# bb_preamp.net
KiCad netlist of a schematic drawn in EAGLE
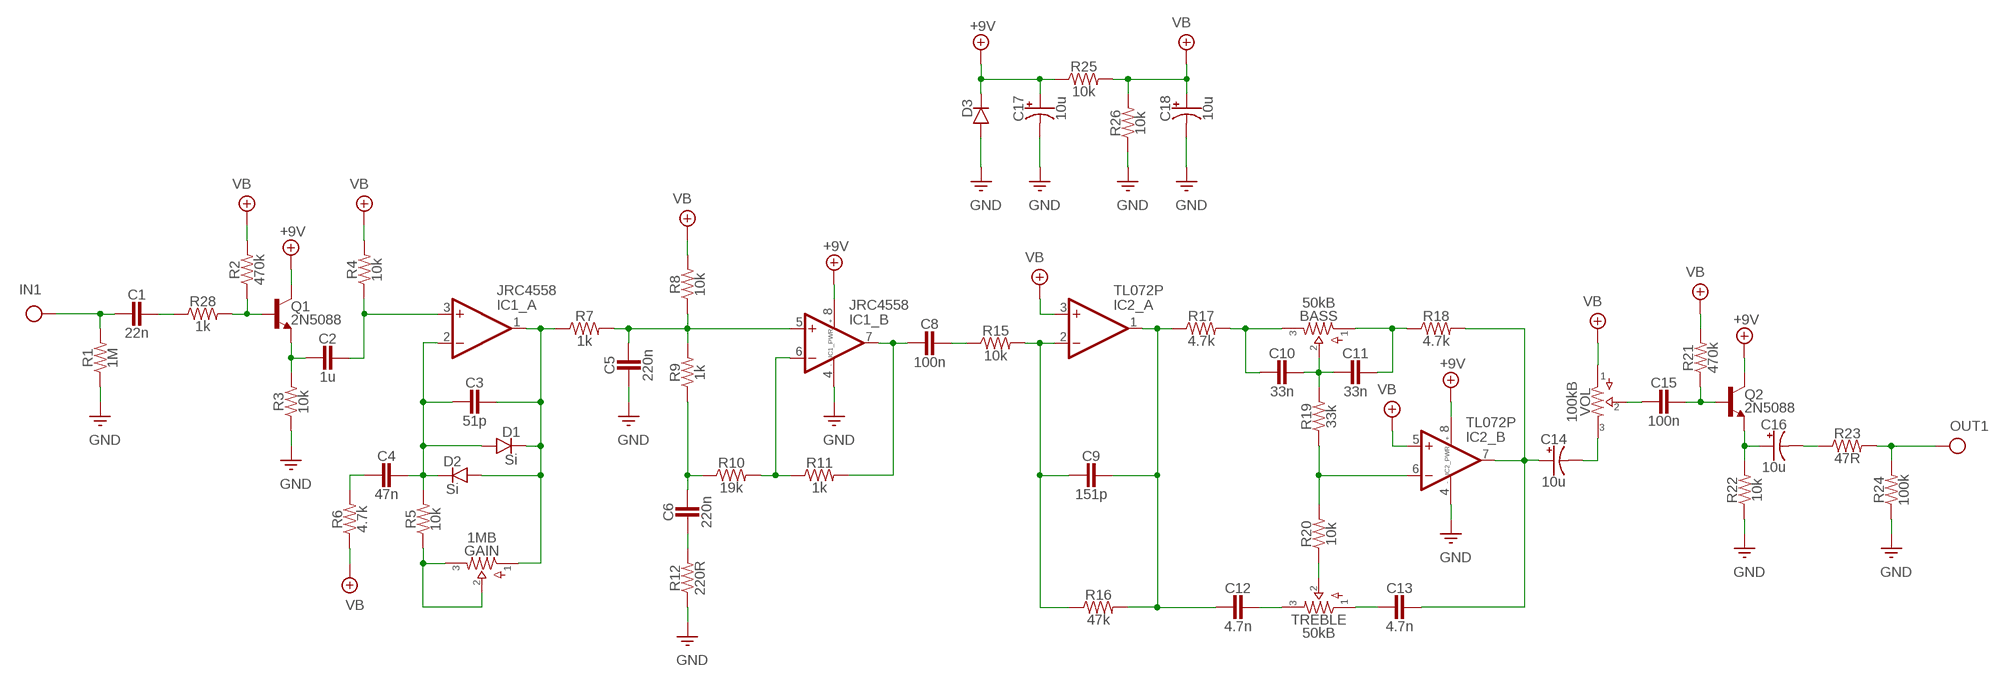
[diagram p0: schematic, sheet 1]

(export (version "E")
  (design (tool "Eeschema 10.0.6"))
  (components
    (comp (ref "BASS")
      (value "50kB")
      (footprint "eagle-import:16MM")
      (libsource (lib "eagle-import") (part "POTS16MM"))
    )
    (comp (ref "C1")
      (value "22n")
      (footprint "eagle-import:BOX_SMALL")
      (libsource (lib "eagle-import") (part "CER/FILMBOX.1"))
    )
    (comp (ref "C2")
      (value "1u")
      (footprint "eagle-import:BOX_SMALL")
      (libsource (lib "eagle-import") (part "CER/FILMBOX.1"))
    )
    (comp (ref "C3")
      (value "51p")
      (footprint "eagle-import:BOX_SMALL")
      (libsource (lib "eagle-import") (part "CER/FILMBOX.1"))
    )
    (comp (ref "C4")
      (value "47n")
      (footprint "eagle-import:BOX_SMALL")
      (libsource (lib "eagle-import") (part "CER/FILMBOX.1"))
    )
    (comp (ref "C5")
      (value "220n")
      (footprint "eagle-import:BOX_SMALL")
      (libsource (lib "eagle-import") (part "CER/FILMBOX.1"))
    )
    (comp (ref "C6")
      (value "220n")
      (footprint "eagle-import:BOX_SMALL")
      (libsource (lib "eagle-import") (part "CER/FILMBOX.1"))
    )
    (comp (ref "C8")
      (value "100n")
      (footprint "eagle-import:BOX_SMALL")
      (libsource (lib "eagle-import") (part "CER/FILMBOX.1"))
    )
    (comp (ref "C9")
      (value "151p")
      (footprint "eagle-import:BOX_SMALL")
      (libsource (lib "eagle-import") (part "CER/FILMBOX.1"))
    )
    (comp (ref "C10")
      (value "33n")
      (footprint "eagle-import:BOX_SMALL")
      (libsource (lib "eagle-import") (part "CER/FILMBOX.1"))
    )
    (comp (ref "C11")
      (value "33n")
      (footprint "eagle-import:BOX_SMALL")
      (libsource (lib "eagle-import") (part "CER/FILMBOX.1"))
    )
    (comp (ref "C12")
      (value "4.7n")
      (footprint "eagle-import:BOX_SMALL")
      (libsource (lib "eagle-import") (part "CER/FILMBOX.1"))
    )
    (comp (ref "C13")
      (value "4.7n")
      (footprint "eagle-import:BOX_SMALL")
      (libsource (lib "eagle-import") (part "CER/FILMBOX.1"))
    )
    (comp (ref "C14")
      (value "10u")
      (footprint "eagle-import:050_020")
      (libsource (lib "eagle-import") (part "0500"))
    )
    (comp (ref "C15")
      (value "100n")
      (footprint "eagle-import:BOX_SMALL")
      (libsource (lib "eagle-import") (part "CER/FILMBOX.1"))
    )
    (comp (ref "C16")
      (value "10u")
      (footprint "eagle-import:050_020")
      (libsource (lib "eagle-import") (part "0500"))
    )
    (comp (ref "C17")
      (value "10u")
      (footprint "eagle-import:050_020")
      (libsource (lib "eagle-import") (part "0500"))
    )
    (comp (ref "C18")
      (value "10u")
      (footprint "eagle-import:050_020")
      (libsource (lib "eagle-import") (part "0500"))
    )
    (comp (ref "D1")
      (value "Si")
      (footprint "eagle-import:DO35-2")
      (libsource (lib "eagle-import") (part "DO35.2"))
    )
    (comp (ref "D2")
      (value "Si")
      (footprint "eagle-import:DO35-2")
      (libsource (lib "eagle-import") (part "DO35.2"))
    )
    (comp (ref "D3")
      (value "DO41.3")
      (footprint "eagle-import:DO41-3")
      (libsource (lib "eagle-import") (part "DO41.3"))
    )
    (comp (ref "GAIN")
      (value "1MB")
      (footprint "eagle-import:16MM")
      (libsource (lib "eagle-import") (part "POTS16MM"))
    )
    (comp (ref "IC1")
      (value "JRC4558")
      (footprint "eagle-import:DIL0")
      (libsource (lib "eagle-import") (part "DUALTH"))
    )
    (comp (ref "IC2")
      (value "TL072P")
      (footprint "eagle-import:DIL0")
      (libsource (lib "eagle-import") (part "DUALTH"))
    )
    (comp (ref "Q1")
      (value "2N5088")
      (footprint "eagle-import:TO92-")
      (libsource (lib "eagle-import") (part "2N5088"))
    )
    (comp (ref "Q2")
      (value "2N5088")
      (footprint "eagle-import:TO92-")
      (libsource (lib "eagle-import") (part "2N5088"))
    )
    (comp (ref "R1")
      (value "1M")
      (footprint "eagle-import:R0207_3")
      (libsource (lib "eagle-import") (part "R_.3B"))
    )
    (comp (ref "R2")
      (value "470k")
      (footprint "eagle-import:R0207_3")
      (libsource (lib "eagle-import") (part "R_.3B"))
    )
    (comp (ref "R3")
      (value "10k")
      (footprint "eagle-import:R0207_3")
      (libsource (lib "eagle-import") (part "R_.3B"))
    )
    (comp (ref "R4")
      (value "10k")
      (footprint "eagle-import:R0207_3")
      (libsource (lib "eagle-import") (part "R_.3B"))
    )
    (comp (ref "R5")
      (value "10k")
      (footprint "eagle-import:R0207_3")
      (libsource (lib "eagle-import") (part "R_.3B"))
    )
    (comp (ref "R6")
      (value "4.7k")
      (footprint "eagle-import:R0207_3")
      (libsource (lib "eagle-import") (part "R_.3B"))
    )
    (comp (ref "R7")
      (value "1k")
      (footprint "eagle-import:R0207_3")
      (libsource (lib "eagle-import") (part "R_.3B"))
    )
    (comp (ref "R8")
      (value "10k")
      (footprint "eagle-import:R0207_3")
      (libsource (lib "eagle-import") (part "R_.3B"))
    )
    (comp (ref "R9")
      (value "1k")
      (footprint "eagle-import:R0207_3")
      (libsource (lib "eagle-import") (part "R_.3B"))
    )
    (comp (ref "R10")
      (value "19k")
      (footprint "eagle-import:R0207_3")
      (libsource (lib "eagle-import") (part "R_.3B"))
    )
    (comp (ref "R11")
      (value "1k")
      (footprint "eagle-import:R0207_3")
      (libsource (lib "eagle-import") (part "R_.3B"))
    )
    (comp (ref "R12")
      (value "220R")
      (footprint "eagle-import:R0207_3")
      (libsource (lib "eagle-import") (part "R_.3B"))
    )
    (comp (ref "R15")
      (value "10k")
      (footprint "eagle-import:R0207_3")
      (libsource (lib "eagle-import") (part "R_.3B"))
    )
    (comp (ref "R16")
      (value "47k")
      (footprint "eagle-import:R0207_3")
      (libsource (lib "eagle-import") (part "R_.3B"))
    )
    (comp (ref "R17")
      (value "4.7k")
      (footprint "eagle-import:R0207_3")
      (libsource (lib "eagle-import") (part "R_.3B"))
    )
    (comp (ref "R18")
      (value "4.7k")
      (footprint "eagle-import:R0207_3")
      (libsource (lib "eagle-import") (part "R_.3B"))
    )
    (comp (ref "R19")
      (value "33k")
      (footprint "eagle-import:R0207_3")
      (libsource (lib "eagle-import") (part "R_.3B"))
    )
    (comp (ref "R20")
      (value "10k")
      (footprint "eagle-import:R0207_3")
      (libsource (lib "eagle-import") (part "R_.3B"))
    )
    (comp (ref "R21")
      (value "470k")
      (footprint "eagle-import:R0207_3")
      (libsource (lib "eagle-import") (part "R_.3B"))
    )
    (comp (ref "R22")
      (value "10k")
      (footprint "eagle-import:R0207_3")
      (libsource (lib "eagle-import") (part "R_.3B"))
    )
    (comp (ref "R23")
      (value "47R")
      (footprint "eagle-import:R0207_3")
      (libsource (lib "eagle-import") (part "R_.3B"))
    )
    (comp (ref "R24")
      (value "100k")
      (footprint "eagle-import:R0207_3")
      (libsource (lib "eagle-import") (part "R_.3B"))
    )
    (comp (ref "R25")
      (value "10k")
      (footprint "eagle-import:R0207_3")
      (libsource (lib "eagle-import") (part "R_.3B"))
    )
    (comp (ref "R26")
      (value "10k")
      (footprint "eagle-import:R0207_3")
      (libsource (lib "eagle-import") (part "R_.3B"))
    )
    (comp (ref "R28")
      (value "1k")
      (footprint "eagle-import:R0207_3")
      (libsource (lib "eagle-import") (part "R_.3B"))
    )
    (comp (ref "TREBLE")
      (value "50kB")
      (footprint "eagle-import:16MM")
      (libsource (lib "eagle-import") (part "POTS16MM"))
    )
    (comp (ref "VOL")
      (value "100kB")
      (footprint "eagle-import:16MM")
      (libsource (lib "eagle-import") (part "POTS16MM"))
    )
  )
  (nets
    (net (code "1") (name "+9V") (class "Default")
      (node (ref "C17") (pin "+") (pinfunction "+_+") (pintype "passive"))
      (node (ref "D3") (pin "C") (pinfunction "C_C") (pintype "passive"))
      (node (ref "IC1") (pin "8") (pinfunction "V+_8") (pintype "power_in"))
      (node (ref "IC2") (pin "8") (pinfunction "V+_8") (pintype "power_in"))
      (node (ref "Q1") (pin "1") (pinfunction "C_1") (pintype "passive"))
      (node (ref "Q2") (pin "1") (pinfunction "C_1") (pintype "passive"))
      (node (ref "R25") (pin "1") (pinfunction "1_1") (pintype "passive"))
    )
    (net (code "2") (name "GND") (class "Default")
      (node (ref "C17") (pin "-") (pinfunction "-_-") (pintype "passive"))
      (node (ref "C18") (pin "-") (pinfunction "-_-") (pintype "passive"))
      (node (ref "C5") (pin "2") (pinfunction "2_2") (pintype "passive"))
      (node (ref "D3") (pin "A") (pinfunction "A_A") (pintype "passive"))
      (node (ref "IC1") (pin "4") (pinfunction "V-_4") (pintype "power_in"))
      (node (ref "IC2") (pin "4") (pinfunction "V-_4") (pintype "power_in"))
      (node (ref "R1") (pin "1") (pinfunction "1_1") (pintype "passive"))
      (node (ref "R12") (pin "1") (pinfunction "1_1") (pintype "passive"))
      (node (ref "R22") (pin "1") (pinfunction "1_1") (pintype "passive"))
      (node (ref "R24") (pin "1") (pinfunction "1_1") (pintype "passive"))
      (node (ref "R26") (pin "1") (pinfunction "1_1") (pintype "passive"))
      (node (ref "R3") (pin "1") (pinfunction "1_1") (pintype "passive"))
    )
    (net (code "3") (name "IN") (class "Default")
      (node (ref "C1") (pin "2") (pinfunction "2_2") (pintype "passive"))
      (node (ref "R1") (pin "2") (pinfunction "2_2") (pintype "passive"))
    )
    (net (code "4") (name "Net-(BASS-Pad1)") (class "Default")
      (node (ref "BASS") (pin "1") (pinfunction "1_1") (pintype "passive"))
      (node (ref "C11") (pin "1") (pinfunction "1_1") (pintype "passive"))
      (node (ref "R18") (pin "1") (pinfunction "1_1") (pintype "passive"))
    )
    (net (code "5") (name "Net-(BASS-Pad2)") (class "Default")
      (node (ref "BASS") (pin "2") (pinfunction "2_2") (pintype "passive"))
      (node (ref "C10") (pin "1") (pinfunction "1_1") (pintype "passive"))
      (node (ref "C11") (pin "2") (pinfunction "2_2") (pintype "passive"))
      (node (ref "R19") (pin "2") (pinfunction "2_2") (pintype "passive"))
    )
    (net (code "6") (name "Net-(BASS-Pad3)") (class "Default")
      (node (ref "BASS") (pin "3") (pinfunction "3_3") (pintype "passive"))
      (node (ref "C10") (pin "2") (pinfunction "2_2") (pintype "passive"))
      (node (ref "R17") (pin "2") (pinfunction "2_2") (pintype "passive"))
    )
    (net (code "7") (name "Net-(C1-Pad1)") (class "Default")
      (node (ref "C1") (pin "1") (pinfunction "1_1") (pintype "passive"))
      (node (ref "R28") (pin "1") (pinfunction "1_1") (pintype "passive"))
    )
    (net (code "8") (name "Net-(C4-Pad2)") (class "Default")
      (node (ref "C4") (pin "2") (pinfunction "2_2") (pintype "passive"))
      (node (ref "R6") (pin "2") (pinfunction "2_2") (pintype "passive"))
    )
    (net (code "9") (name "Net-(C6-Pad1)") (class "Default")
      (node (ref "C6") (pin "1") (pinfunction "1_1") (pintype "passive"))
      (node (ref "R10") (pin "1") (pinfunction "1_1") (pintype "passive"))
      (node (ref "R9") (pin "1") (pinfunction "1_1") (pintype "passive"))
    )
    (net (code "10") (name "Net-(C6-Pad2)") (class "Default")
      (node (ref "C6") (pin "2") (pinfunction "2_2") (pintype "passive"))
      (node (ref "R12") (pin "2") (pinfunction "2_2") (pintype "passive"))
    )
    (net (code "11") (name "Net-(C8-Pad1)") (class "Default")
      (node (ref "C8") (pin "1") (pinfunction "1_1") (pintype "passive"))
      (node (ref "R15") (pin "1") (pinfunction "1_1") (pintype "passive"))
    )
    (net (code "12") (name "Net-(C12-Pad1)") (class "Default")
      (node (ref "C12") (pin "1") (pinfunction "1_1") (pintype "passive"))
      (node (ref "TREBLE") (pin "3") (pinfunction "3_3") (pintype "passive"))
    )
    (net (code "13") (name "Net-(C13-Pad2)") (class "Default")
      (node (ref "C13") (pin "2") (pinfunction "2_2") (pintype "passive"))
      (node (ref "TREBLE") (pin "1") (pinfunction "1_1") (pintype "passive"))
    )
    (net (code "14") (name "Net-(C14-Pad-)") (class "Default")
      (node (ref "C14") (pin "-") (pinfunction "-_-") (pintype "passive"))
      (node (ref "VOL") (pin "3") (pinfunction "3_3") (pintype "passive"))
    )
    (net (code "15") (name "Net-(C15-Pad2)") (class "Default")
      (node (ref "C15") (pin "2") (pinfunction "2_2") (pintype "passive"))
      (node (ref "VOL") (pin "2") (pinfunction "2_2") (pintype "passive"))
    )
    (net (code "16") (name "Net-(C16-Pad-)") (class "Default")
      (node (ref "C16") (pin "-") (pinfunction "-_-") (pintype "passive"))
      (node (ref "R23") (pin "1") (pinfunction "1_1") (pintype "passive"))
    )
    (net (code "17") (name "Net-(GAIN-Pad2)") (class "Default")
      (node (ref "GAIN") (pin "2") (pinfunction "2_2") (pintype "passive"))
      (node (ref "GAIN") (pin "3") (pinfunction "3_3") (pintype "passive"))
      (node (ref "R5") (pin "1") (pinfunction "1_1") (pintype "passive"))
    )
    (net (code "18") (name "Net-(IC1A-+IN)") (class "Default")
      (node (ref "C2") (pin "1") (pinfunction "1_1") (pintype "passive"))
      (node (ref "IC1") (pin "3") (pinfunction "+IN_3") (pintype "input"))
      (node (ref "R4") (pin "1") (pinfunction "1_1") (pintype "passive"))
    )
    (net (code "19") (name "Net-(IC1A--IN)") (class "Default")
      (node (ref "C3") (pin "2") (pinfunction "2_2") (pintype "passive"))
      (node (ref "C4") (pin "1") (pinfunction "1_1") (pintype "passive"))
      (node (ref "D1") (pin "A") (pinfunction "A_A") (pintype "passive"))
      (node (ref "D2") (pin "C") (pinfunction "C_C") (pintype "passive"))
      (node (ref "IC1") (pin "2") (pinfunction "-IN_2") (pintype "input"))
      (node (ref "R5") (pin "2") (pinfunction "2_2") (pintype "passive"))
    )
    (net (code "20") (name "Net-(IC1A-OUT)") (class "Default")
      (node (ref "C3") (pin "1") (pinfunction "1_1") (pintype "passive"))
      (node (ref "D1") (pin "C") (pinfunction "C_C") (pintype "passive"))
      (node (ref "D2") (pin "A") (pinfunction "A_A") (pintype "passive"))
      (node (ref "GAIN") (pin "1") (pinfunction "1_1") (pintype "passive"))
      (node (ref "IC1") (pin "1") (pinfunction "OUT_1") (pintype "output"))
      (node (ref "R7") (pin "1") (pinfunction "1_1") (pintype "passive"))
    )
    (net (code "21") (name "Net-(IC1B-+IN)") (class "Default")
      (node (ref "C5") (pin "1") (pinfunction "1_1") (pintype "passive"))
      (node (ref "IC1") (pin "5") (pinfunction "+IN_5") (pintype "input"))
      (node (ref "R7") (pin "2") (pinfunction "2_2") (pintype "passive"))
      (node (ref "R8") (pin "1") (pinfunction "1_1") (pintype "passive"))
      (node (ref "R9") (pin "2") (pinfunction "2_2") (pintype "passive"))
    )
    (net (code "22") (name "Net-(IC1B--IN)") (class "Default")
      (node (ref "IC1") (pin "6") (pinfunction "-IN_6") (pintype "input"))
      (node (ref "R10") (pin "2") (pinfunction "2_2") (pintype "passive"))
      (node (ref "R11") (pin "1") (pinfunction "1_1") (pintype "passive"))
    )
    (net (code "23") (name "Net-(IC1B-OUT)") (class "Default")
      (node (ref "C8") (pin "2") (pinfunction "2_2") (pintype "passive"))
      (node (ref "IC1") (pin "7") (pinfunction "OUT_7") (pintype "output"))
      (node (ref "R11") (pin "2") (pinfunction "2_2") (pintype "passive"))
    )
    (net (code "24") (name "Net-(IC2A--IN)") (class "Default")
      (node (ref "C9") (pin "2") (pinfunction "2_2") (pintype "passive"))
      (node (ref "IC2") (pin "2") (pinfunction "-IN_2") (pintype "input"))
      (node (ref "R15") (pin "2") (pinfunction "2_2") (pintype "passive"))
      (node (ref "R16") (pin "1") (pinfunction "1_1") (pintype "passive"))
    )
    (net (code "25") (name "Net-(IC2A-OUT)") (class "Default")
      (node (ref "C12") (pin "2") (pinfunction "2_2") (pintype "passive"))
      (node (ref "C9") (pin "1") (pinfunction "1_1") (pintype "passive"))
      (node (ref "IC2") (pin "1") (pinfunction "OUT_1") (pintype "output"))
      (node (ref "R16") (pin "2") (pinfunction "2_2") (pintype "passive"))
      (node (ref "R17") (pin "1") (pinfunction "1_1") (pintype "passive"))
    )
    (net (code "26") (name "Net-(IC2B--IN)") (class "Default")
      (node (ref "IC2") (pin "6") (pinfunction "-IN_6") (pintype "input"))
      (node (ref "R19") (pin "1") (pinfunction "1_1") (pintype "passive"))
      (node (ref "R20") (pin "2") (pinfunction "2_2") (pintype "passive"))
    )
    (net (code "27") (name "Net-(IC2B-OUT)") (class "Default")
      (node (ref "C13") (pin "1") (pinfunction "1_1") (pintype "passive"))
      (node (ref "C14") (pin "+") (pinfunction "+_+") (pintype "passive"))
      (node (ref "IC2") (pin "7") (pinfunction "OUT_7") (pintype "output"))
      (node (ref "R18") (pin "2") (pinfunction "2_2") (pintype "passive"))
    )
    (net (code "28") (name "Net-(Q1-B)") (class "Default")
      (node (ref "Q1") (pin "2") (pinfunction "B_2") (pintype "passive"))
      (node (ref "R2") (pin "1") (pinfunction "1_1") (pintype "passive"))
      (node (ref "R28") (pin "2") (pinfunction "2_2") (pintype "passive"))
    )
    (net (code "29") (name "Net-(Q1-E)") (class "Default")
      (node (ref "C2") (pin "2") (pinfunction "2_2") (pintype "passive"))
      (node (ref "Q1") (pin "3") (pinfunction "E_3") (pintype "passive"))
      (node (ref "R3") (pin "2") (pinfunction "2_2") (pintype "passive"))
    )
    (net (code "30") (name "Net-(Q2-B)") (class "Default")
      (node (ref "C15") (pin "1") (pinfunction "1_1") (pintype "passive"))
      (node (ref "Q2") (pin "2") (pinfunction "B_2") (pintype "passive"))
      (node (ref "R21") (pin "1") (pinfunction "1_1") (pintype "passive"))
    )
    (net (code "31") (name "Net-(Q2-E)") (class "Default")
      (node (ref "C16") (pin "+") (pinfunction "+_+") (pintype "passive"))
      (node (ref "Q2") (pin "3") (pinfunction "E_3") (pintype "passive"))
      (node (ref "R22") (pin "2") (pinfunction "2_2") (pintype "passive"))
    )
    (net (code "32") (name "Net-(R20-Pad1)") (class "Default")
      (node (ref "R20") (pin "1") (pinfunction "1_1") (pintype "passive"))
      (node (ref "TREBLE") (pin "2") (pinfunction "2_2") (pintype "passive"))
    )
    (net (code "33") (name "OUT") (class "Default")
      (node (ref "R23") (pin "2") (pinfunction "2_2") (pintype "passive"))
      (node (ref "R24") (pin "2") (pinfunction "2_2") (pintype "passive"))
    )
    (net (code "34") (name "VB") (class "Default")
      (node (ref "C18") (pin "+") (pinfunction "+_+") (pintype "passive"))
      (node (ref "IC2") (pin "3") (pinfunction "+IN_3") (pintype "input"))
      (node (ref "IC2") (pin "5") (pinfunction "+IN_5") (pintype "input"))
      (node (ref "R2") (pin "2") (pinfunction "2_2") (pintype "passive"))
      (node (ref "R21") (pin "2") (pinfunction "2_2") (pintype "passive"))
      (node (ref "R25") (pin "2") (pinfunction "2_2") (pintype "passive"))
      (node (ref "R26") (pin "2") (pinfunction "2_2") (pintype "passive"))
      (node (ref "R4") (pin "2") (pinfunction "2_2") (pintype "passive"))
      (node (ref "R6") (pin "1") (pinfunction "1_1") (pintype "passive"))
      (node (ref "R8") (pin "2") (pinfunction "2_2") (pintype "passive"))
      (node (ref "VOL") (pin "1") (pinfunction "1_1") (pintype "passive"))
    )
  )
)
